# PSU_LT1962_4V8.net
KiCad netlist of a schematic drawn in Altium Designer
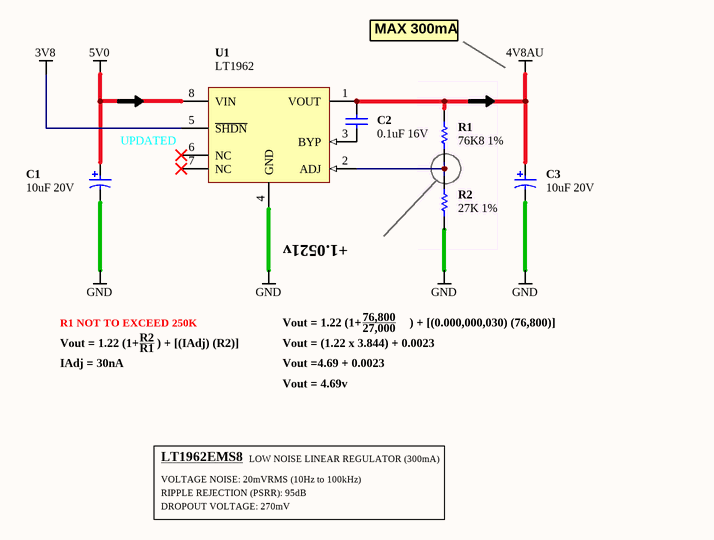
[diagram p0: PSU_LT1962_4V8.SchDoc]

(export (version "E")
  (design (tool "Eeschema 10.0.6"))
  (components
    (comp (ref "C1")
      (value "10uF 20V")
      (footprint "CAPC3528-STAR")
      (description "Capacitor, Tantalum, 10uF 10% 20V MCCT-B (3528)")
      (fields (field (name "TOLERANCE") "10 %"))
      (libsource (lib "AltiumDesignLibrary") (part "CAP-P"))
    )
    (comp (ref "C2")
      (value "0.1uF 16V")
      (footprint "CAPC1005-STAR")
      (description "Capacitor, Ceramic, 0.1uF 10% 16V 0402 (1005) X7R")
      (fields (field (name "TOLERANCE") "10 %"))
      (libsource (lib "AltiumDesignLibrary") (part "D-101-0080"))
    )
    (comp (ref "C3")
      (value "10uF 20V")
      (footprint "CAPC3528-STAR")
      (description "Capacitor, Tantalum, 10uF 10% 20V MCCT-B (3528)")
      (fields (field (name "TOLERANCE") "10 %"))
      (libsource (lib "AltiumDesignLibrary") (part "CAP-P"))
    )
    (comp (ref "R1")
      (value "76K8 1%")
      (footprint "RESC1005-STAR")
      (description "Resistor, 76K8 1% 0402 (1005)")
      (fields (field (name "TOLERANCE") "1 %"))
      (libsource (lib "AltiumDesignLibrary") (part "RES"))
    )
    (comp (ref "R2")
      (value "27K 1%")
      (footprint "RESC1005-STAR")
      (description "Resistor, 27K 1% 0402 (1005)")
      (fields (field (name "TOLERANCE") "1 %"))
      (libsource (lib "AltiumDesignLibrary") (part "RES"))
    )
    (comp (ref "U1")
      (value "LT1962")
      (footprint "TSOP65P490-8AN")
      (description "300mA, Low Noise,  Micropower  LDO Regulators")
      (libsource (lib "AltiumDesignLibrary") (part "LT1962"))
    )
  )
  (nets
    (net (code "1") (name "3V8") (class "Default")
      (node (ref "U1") (pin "5") (pinfunction "~{SHDN}_5") (pintype "power_in"))
    )
    (net (code "2") (name "4V8AU") (class "Default")
      (node (ref "C2") (pin "2") (pinfunction "2_2") (pintype "passive"))
      (node (ref "C3") (pin "1") (pinfunction "1_1") (pintype "passive"))
      (node (ref "R1") (pin "1") (pinfunction "1_1") (pintype "passive"))
      (node (ref "U1") (pin "1") (pinfunction "VOUT_1") (pintype "power_in"))
    )
    (net (code "3") (name "5V0") (class "Default")
      (node (ref "C1") (pin "1") (pinfunction "1_1") (pintype "passive"))
      (node (ref "U1") (pin "8") (pinfunction "VIN_8") (pintype "power_in"))
    )
    (net (code "4") (name "GND") (class "Default")
      (node (ref "C1") (pin "2") (pinfunction "2_2") (pintype "passive"))
      (node (ref "C3") (pin "2") (pinfunction "2_2") (pintype "passive"))
      (node (ref "R2") (pin "2") (pinfunction "2_2") (pintype "passive"))
      (node (ref "U1") (pin "4") (pinfunction "GND_4") (pintype "power_in"))
    )
    (net (code "5") (name "Net-(U1-ADJ)") (class "Default")
      (node (ref "R1") (pin "2") (pinfunction "2_2") (pintype "passive"))
      (node (ref "R2") (pin "1") (pinfunction "1_1") (pintype "passive"))
      (node (ref "U1") (pin "2") (pinfunction "ADJ_2") (pintype "input"))
    )
    (net (code "6") (name "Net-(U1-BYP)") (class "Default")
      (node (ref "C2") (pin "1") (pinfunction "1_1") (pintype "passive"))
      (node (ref "U1") (pin "3") (pinfunction "BYP_3") (pintype "input"))
    )
    (net (code "7") (name "unconnected-(U1-NC-Pad6)") (class "Default")
      (node (ref "U1") (pin "6") (pinfunction "NC_6") (pintype "power_in+no_connect"))
    )
    (net (code "8") (name "unconnected-(U1-NC-Pad7)") (class "Default")
      (node (ref "U1") (pin "7") (pinfunction "NC_7") (pintype "power_in+no_connect"))
    )
  )
)
